# Nano_1.net
KiCad netlist of a schematic drawn in Altium Designer
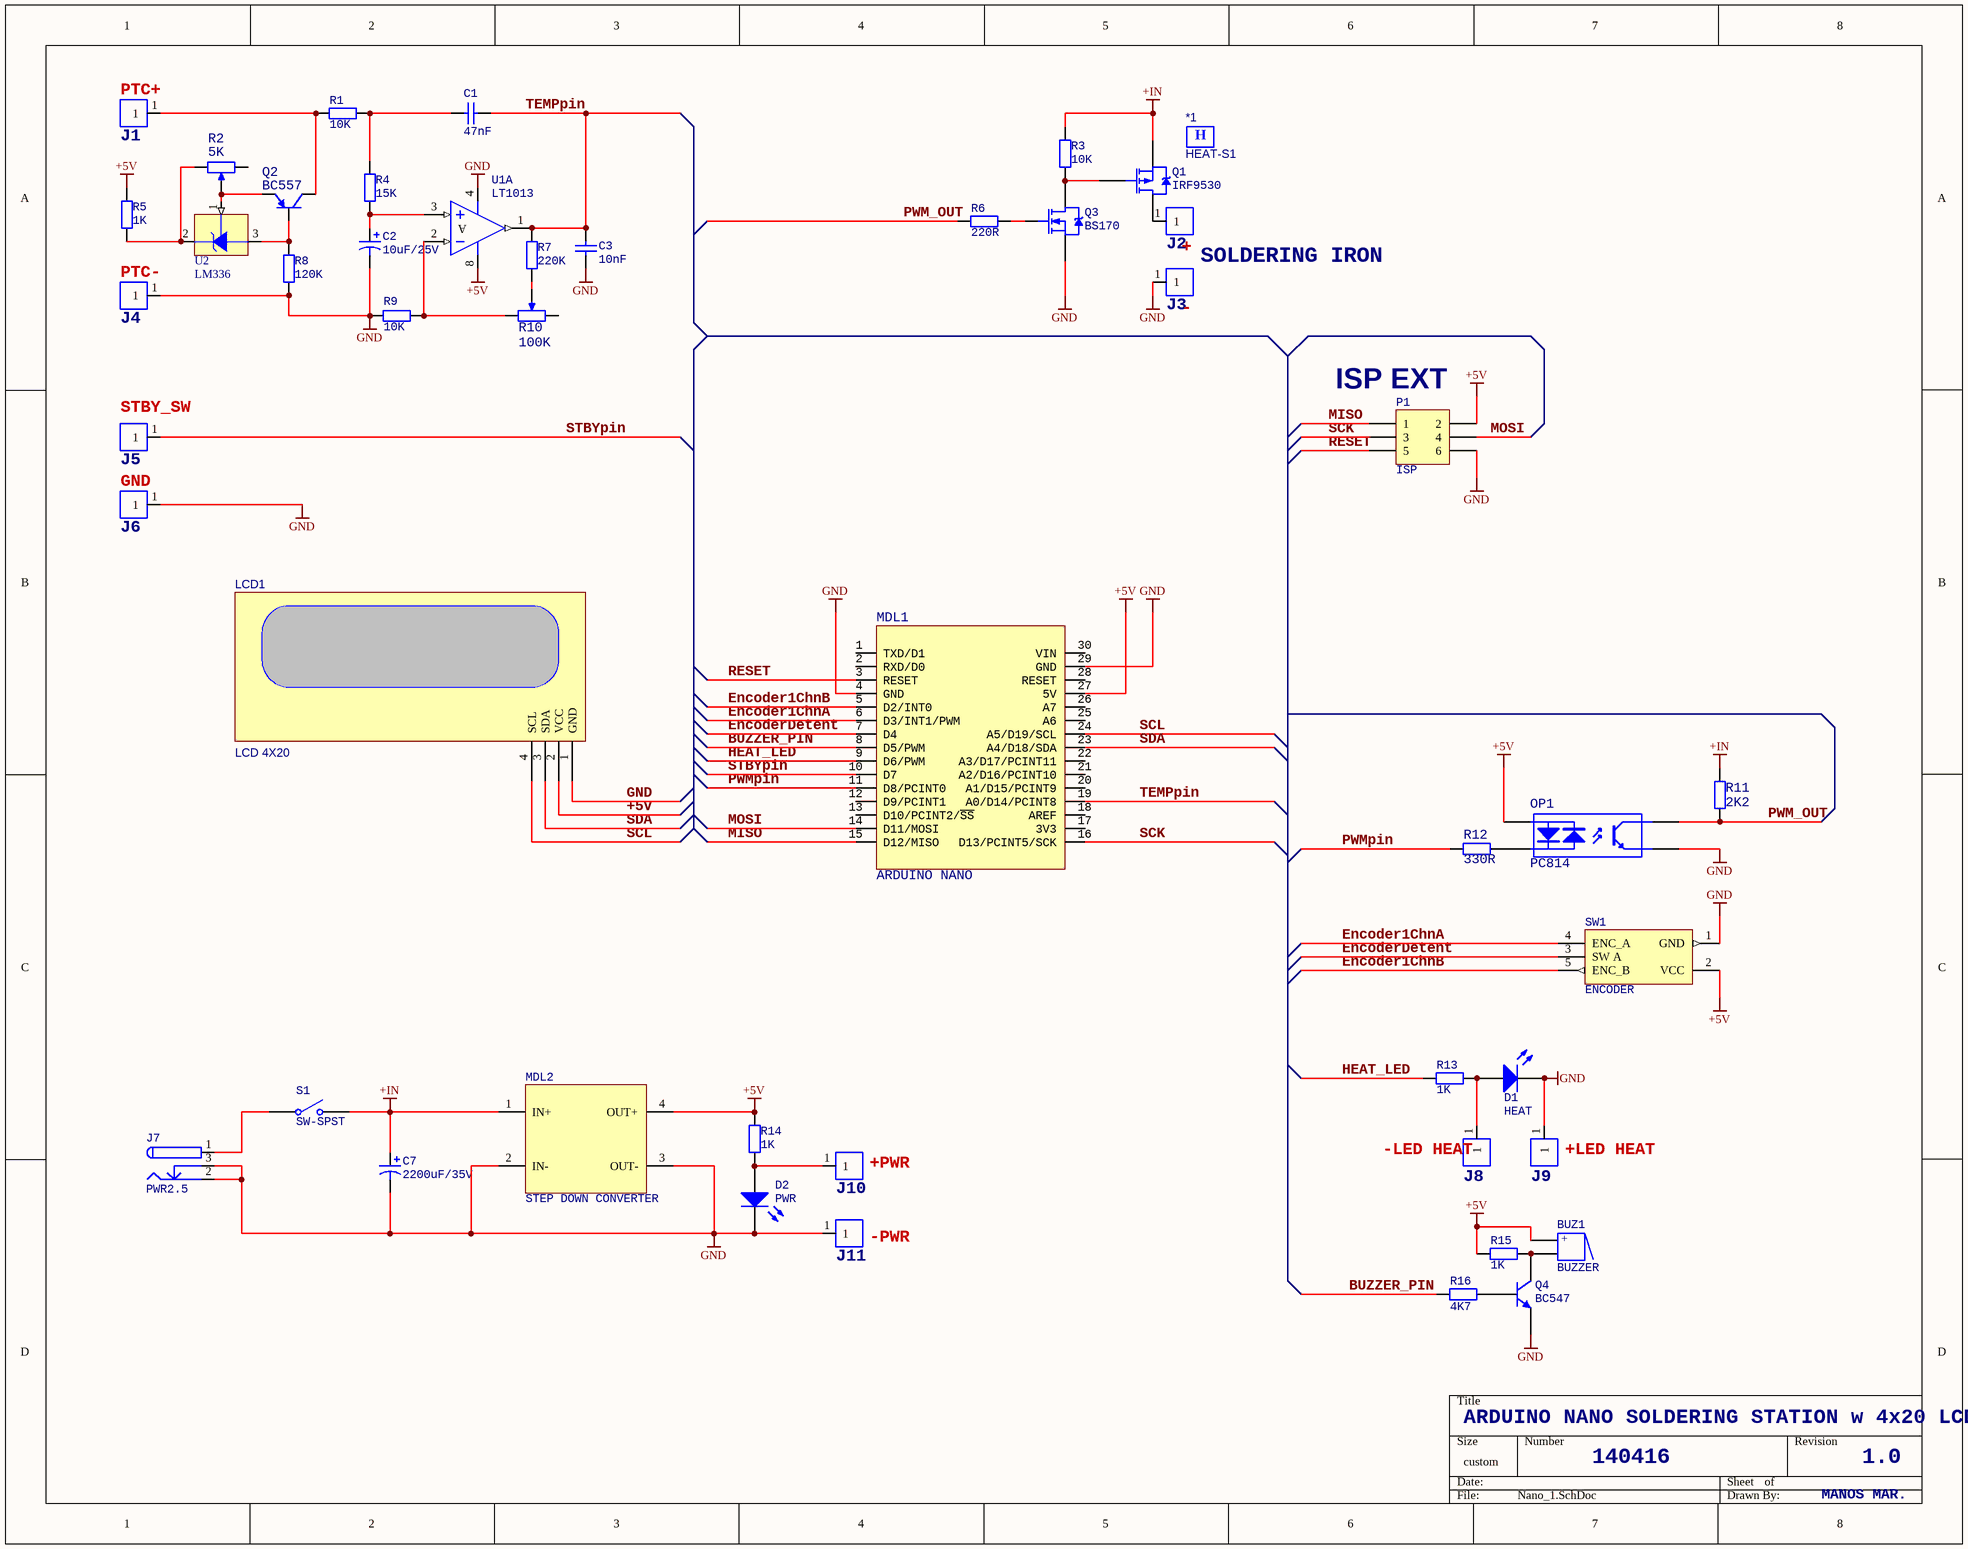
[diagram p0: Nano_1.SchDoc]

(export (version "E")
  (design (tool "Eeschema 10.0.6"))
  (components
    (comp (ref "*1")
      (value "HEAT-S1")
      (footprint "SK 104 HEATSHINK")
      (libsource (lib "SG_INTLIB") (part "HEAT-S1"))
    )
    (comp (ref "BUZ1") (value "BUZZER") (footprint "BUZZER") (libsource (lib "SMD STATION") (part "BUZZER")))
    (comp (ref "C1")
      (value "47nF")
      (footprint "RAD0.2")
      (description "Capacitor, Ceramic, 4.7uF 10% 16V 0805 (2012) X7R")
      (fields (field (name "TOLERANCE") "10 %"))
      (libsource (lib "AltiumDesignLibrary") (part "CAP-NP"))
    )
    (comp (ref "C2")
      (value "10uF/25V")
      (footprint "RB-08")
      (description "Polarized Capacitor (Radial)")
      (fields (field (name "PUBLISHER") "Altium Limited"))
      (libsource (lib "Miscellaneous Devices") (part "Cap Pol1"))
    )
    (comp (ref "C3")
      (value "10nF")
      (footprint "RAD0.2")
      (description "Capacitor, Ceramic, 4.7uF 10% 16V 0805 (2012) X7R")
      (fields (field (name "TOLERANCE") "10 %"))
      (libsource (lib "AltiumDesignLibrary") (part "CAP-NP"))
    )
    (comp (ref "C7")
      (value "2200uF/35V")
      (footprint "RB5-10.5")
      (description "Polarized Capacitor (Radial)")
      (fields (field (name "PUBLISHER") "Altium Limited"))
      (libsource (lib "Miscellaneous Devices") (part "Cap Pol1"))
    )
    (comp (ref "D1")
      (value "HEAT")
      (footprint "LED0.3")
      (description "Typical INFRARED GaAs LED")
      (fields (field (name "PUBLISHER") "Altium Limited"))
      (libsource (lib "Miscellaneous Devices") (part "LED0"))
    )
    (comp (ref "D2")
      (value "PWR")
      (footprint "LED0.3")
      (description "Typical INFRARED GaAs LED")
      (fields (field (name "PUBLISHER") "Altium Limited"))
      (libsource (lib "Miscellaneous Devices") (part "LED0"))
    )
    (comp (ref "J1")
      (value "PTC+")
      (footprint "CON2")
      (fields (field (name "MANUFACTURER") "Sta.Ge HELLAS"))
      (libsource (lib "Z_General_SCH_Library") (part "CON1_S"))
    )
    (comp (ref "J2")
      (value "+")
      (footprint "CON2")
      (fields (field (name "MANUFACTURER") "Sta.Ge HELLAS"))
      (libsource (lib "") (part "CON1_S_1"))
    )
    (comp (ref "J3")
      (value "-")
      (footprint "CON2")
      (fields (field (name "MANUFACTURER") "Sta.Ge HELLAS"))
      (libsource (lib "") (part "CON1_S_1"))
    )
    (comp (ref "J4")
      (value "PTC-")
      (footprint "CON2")
      (fields (field (name "MANUFACTURER") "Sta.Ge HELLAS"))
      (libsource (lib "Z_General_SCH_Library") (part "CON1_S"))
    )
    (comp (ref "J5")
      (value "STBY_SW")
      (footprint "CON2")
      (fields (field (name "MANUFACTURER") "Sta.Ge HELLAS"))
      (libsource (lib "Z_General_SCH_Library") (part "CON1_S"))
    )
    (comp (ref "J6")
      (value "GND")
      (footprint "CON2")
      (fields (field (name "MANUFACTURER") "Sta.Ge HELLAS"))
      (libsource (lib "Z_General_SCH_Library") (part "CON1_S"))
    )
    (comp (ref "J7")
      (value "PWR2.5")
      (footprint "POWER JACK")
      (description "Low Voltage Power Supply Connector")
      (fields (field (name "PUBLISHER") "Altium Limited"))
      (libsource (lib "Miscellaneous Connectors") (part "PWR2.5"))
    )
    (comp (ref "J8")
      (value "-LED HEAT")
      (footprint "CON2")
      (fields (field (name "MANUFACTURER") "Sta.Ge HELLAS"))
      (libsource (lib "") (part "CON1_S_2"))
    )
    (comp (ref "J9")
      (value "+LED HEAT")
      (footprint "CON2")
      (fields (field (name "MANUFACTURER") "Sta.Ge HELLAS"))
      (libsource (lib "") (part "CON1_S_2"))
    )
    (comp (ref "J10")
      (value "+PWR")
      (footprint "CON2")
      (fields (field (name "MANUFACTURER") "Sta.Ge HELLAS"))
      (libsource (lib "") (part "CON1_S_1"))
    )
    (comp (ref "J11")
      (value "-PWR")
      (footprint "CON2")
      (fields (field (name "MANUFACTURER") "Sta.Ge HELLAS"))
      (libsource (lib "") (part "CON1_S_1"))
    )
    (comp (ref "LCD1")
      (value "LCD 4X20")
      (footprint "HDR1X4")
      (fields (field (name "Comment") "LCD 4x20 SERIAL"))
      (libsource (lib "DDS_") (part "LCD4X20"))
    )
    (comp (ref "MDL1")
      (value "ARDUINO NANO")
      (footprint "ARDUINO NANO")
      (libsource (lib "SMD STATION") (part "ARDUINO NANO"))
    )
    (comp (ref "MDL2")
      (value "STEP DOWN CONVERTER")
      (footprint "STEP DOWN CONVERTER MINI")
      (libsource (lib "SMD STATION") (part "STEP DOWN CONVERTER"))
    )
    (comp (ref "OP1")
      (value "PC814")
      (footprint "DIP-4")
      (description "AC OPTOCUPLER")
      (libsource (lib "STAGE_MP3") (part "OPTO-AC1"))
    )
    (comp (ref "P1")
      (value "ISP")
      (footprint "HDR2X3")
      (description "Header, 3-Pin, Dual row")
      (fields (field (name "PUBLISHER") "Altium Limited"))
      (libsource (lib "Miscellaneous Connectors") (part "Header 3X2"))
    )
    (comp (ref "Q1")
      (value "IRF9530")
      (footprint "TO-220V")
      (description "P-Channel Power MOSFET")
      (fields (field (name "PUBLISHER") "Altium Limited"))
      (libsource (lib "Miscellaneous Devices") (part "PMOS-2"))
    )
    (comp (ref "Q2")
      (value "BC557")
      (footprint "T0-92")
      (description "PNP Bipolar Transistor")
      (fields (field (name "PUBLISHER") "Altium Limited"))
      (libsource (lib "Miscellaneous Devices") (part "PNP"))
    )
    (comp (ref "Q3")
      (value "BS170")
      (footprint "T0-92")
      (description "N-Channel Power MOSFET")
      (fields (field (name "PUBLISHER") "Altium Limited"))
      (libsource (lib "Miscellaneous Devices") (part "NMOS-2"))
    )
    (comp (ref "Q4")
      (value "BC547")
      (footprint "T0-92")
      (description "NPN Bipolar Transistor")
      (fields (field (name "PUBLISHER") "Altium Limited"))
      (libsource (lib "Miscellaneous Devices") (part "NPN"))
    )
    (comp (ref "R1")
      (value "10K")
      (footprint "AXIAL0.4")
      (fields
        (field (name "MANUFACTURER") "Generic Components")
        (field (name "POWER") "0,2W")
        (field (name "SGPARTNUMBER") "R001051")
        (field (name "PUBLISHER") "Altium Limited")
      )
      (libsource (lib "") (part "RES_1"))
    )
    (comp (ref "R2")
      (value "5K")
      (footprint "VR6")
      (fields
        (field (name "MANUFACTURER") "Sta.Ge HELLAS")
        (field (name "SGPARTNUMBER") "R001049")
        (field (name "PART NUMBER") "R002107")
        (field (name "PUBLISHER") "Altium Limited")
      )
      (libsource (lib "") (part "RPot2_1"))
    )
    (comp (ref "R3")
      (value "10K")
      (footprint "AXIAL0.4")
      (description "Resistor")
      (fields (field (name "PUBLISHER") "Altium Limited"))
      (libsource (lib "") (part "Res2_1"))
    )
    (comp (ref "R4")
      (value "15K")
      (footprint "AXIAL0.4")
      (fields
        (field (name "MANUFACTURER") "Generic Components")
        (field (name "POWER") "0,2W")
        (field (name "SGPARTNUMBER") "R001051")
        (field (name "PUBLISHER") "Altium Limited")
      )
      (libsource (lib "") (part "RES_3"))
    )
    (comp (ref "R5")
      (value "1K")
      (footprint "AXIAL0.4")
      (fields
        (field (name "MANUFACTURER") "Generic Components")
        (field (name "POWER") "0,2W")
        (field (name "SGPARTNUMBER") "R001051")
        (field (name "PUBLISHER") "Altium Limited")
      )
      (libsource (lib "SG_PCB") (part "RES"))
    )
    (comp (ref "R6")
      (value "220R")
      (footprint "AXIAL0.4")
      (description "Resistor")
      (fields (field (name "PUBLISHER") "Altium Limited"))
      (libsource (lib "Miscellaneous Devices") (part "Res2"))
    )
    (comp (ref "R7")
      (value "220K")
      (footprint "AXIAL0.4")
      (fields
        (field (name "MANUFACTURER") "Generic Components")
        (field (name "POWER") "0,2W")
        (field (name "SGPARTNUMBER") "R001051")
        (field (name "PUBLISHER") "Altium Limited")
      )
      (libsource (lib "") (part "RES_3"))
    )
    (comp (ref "R8")
      (value "120K")
      (footprint "AXIAL0.4")
      (fields
        (field (name "MANUFACTURER") "Generic Components")
        (field (name "POWER") "0,2W")
        (field (name "SGPARTNUMBER") "R001051")
        (field (name "PUBLISHER") "Altium Limited")
      )
      (libsource (lib "SG_PCB") (part "RES"))
    )
    (comp (ref "R9")
      (value "10K")
      (footprint "AXIAL0.4")
      (fields
        (field (name "MANUFACTURER") "Generic Components")
        (field (name "POWER") "0,2W")
        (field (name "SGPARTNUMBER") "R001051")
        (field (name "PUBLISHER") "Altium Limited")
      )
      (libsource (lib "") (part "RES_2"))
    )
    (comp (ref "R10")
      (value "100K")
      (footprint "VR6")
      (fields
        (field (name "MANUFACTURER") "Sta.Ge HELLAS")
        (field (name "SGPARTNUMBER") "R001049")
        (field (name "PART NUMBER") "R002107")
        (field (name "PUBLISHER") "Altium Limited")
      )
      (libsource (lib "SG_INTLIB") (part "RPot2"))
    )
    (comp (ref "R11")
      (value "2K2")
      (footprint "AXIAL0.4")
      (fields
        (field (name "MANUFACTURER") "Generic Components")
        (field (name "POWER") "0,2W")
        (field (name "SGPARTNUMBER") "R001051")
        (field (name "PUBLISHER") "Altium Limited")
      )
      (libsource (lib "") (part "RES_3"))
    )
    (comp (ref "R12")
      (value "330R")
      (footprint "AXIAL0.4")
      (fields
        (field (name "MANUFACTURER") "Generic Components")
        (field (name "POWER") "0,2W")
        (field (name "SGPARTNUMBER") "R001051")
        (field (name "PUBLISHER") "Altium Limited")
      )
      (libsource (lib "") (part "RES_2"))
    )
    (comp (ref "R13")
      (value "1K")
      (footprint "AXIAL0.4")
      (description "Resistor")
      (fields (field (name "PUBLISHER") "Altium Limited"))
      (libsource (lib "Miscellaneous Devices") (part "Res2"))
    )
    (comp (ref "R14")
      (value "1K")
      (footprint "AXIAL0.4")
      (description "Resistor")
      (fields (field (name "PUBLISHER") "Altium Limited"))
      (libsource (lib "") (part "Res2_1"))
    )
    (comp (ref "R15")
      (value "1K")
      (footprint "AXIAL0.4")
      (fields
        (field (name "MANUFACTURER") "Generic Components")
        (field (name "POWER") "0,2W")
        (field (name "SGPARTNUMBER") "R001051")
        (field (name "PUBLISHER") "Altium Limited")
      )
      (libsource (lib "") (part "RES_2"))
    )
    (comp (ref "R16")
      (value "4K7")
      (footprint "AXIAL0.4")
      (fields
        (field (name "MANUFACTURER") "Generic Components")
        (field (name "POWER") "0,2W")
        (field (name "SGPARTNUMBER") "R001051")
        (field (name "PUBLISHER") "Altium Limited")
      )
      (libsource (lib "") (part "RES_1"))
    )
    (comp (ref "S1")
      (value "SW-SPST")
      (footprint "SPST-2")
      (description "Single-Pole, Single-Throw Switch")
      (fields (field (name "PUBLISHER") "Altium Limited"))
      (libsource (lib "Miscellaneous Devices") (part "SW-SPST"))
    )
    (comp (ref "SW1")
      (value "ENCODER")
      (footprint "HDR1X5")
      (libsource (lib "SMD STATION") (part "ROTARY ENC"))
    )
    (comp (ref "U1")
      (value "LT1013")
      (footprint "DIP-8")
      (description "Dual Precision Operational Amplifier")
      (fields (field (name "PUBLISHER") "Altium Limited"))
      (libsource (lib "LT Operational Amplifier") (part "LT1013ACJ8"))
    )
    (comp (ref "U2")
      (value "LM336")
      (footprint "Z03A")
      (description "Adjustable Micropower Voltage Reference")
      (fields (field (name "PUBLISHER") "Altium Limited"))
      (libsource (lib "NSC Power Mgt Voltage Reference") (part "LM385Z"))
    )
  )
  (nets
    (net (code "1") (name "+5V") (class "Default")
      (node (ref "BUZ1") (pin "1") (pinfunction "1_1") (pintype "passive"))
      (node (ref "LCD1") (pin "2") (pinfunction "VCC_2") (pintype "passive"))
      (node (ref "MDL1") (pin "27") (pinfunction "5V_27") (pintype "passive"))
      (node (ref "MDL2") (pin "4") (pinfunction "OUT+_4") (pintype "passive"))
      (node (ref "OP1") (pin "1") (pinfunction "A_1") (pintype "passive"))
      (node (ref "P1") (pin "2") (pinfunction "2_2") (pintype "passive"))
      (node (ref "R14") (pin "2") (pinfunction "2_2") (pintype "passive"))
      (node (ref "R15") (pin "2") (pinfunction "2_2") (pintype "passive"))
      (node (ref "R5") (pin "2") (pinfunction "2_2") (pintype "passive"))
      (node (ref "SW1") (pin "2") (pinfunction "VCC_2") (pintype "passive"))
      (node (ref "U1") (pin "8") (pinfunction "V+_8") (pintype "power_in"))
    )
    (net (code "2") (name "+IN") (class "Default")
      (node (ref "C7") (pin "1") (pinfunction "1_1") (pintype "passive"))
      (node (ref "MDL2") (pin "1") (pinfunction "IN+_1") (pintype "passive"))
      (node (ref "Q1") (pin "3") (pinfunction "S_3") (pintype "passive"))
      (node (ref "R11") (pin "1") (pinfunction "1_1") (pintype "passive"))
      (node (ref "R3") (pin "2") (pinfunction "2_2") (pintype "passive"))
      (node (ref "S1") (pin "2") (pinfunction "NO_2") (pintype "passive"))
    )
    (net (code "3") (name "/BUZZER_PIN") (class "Default")
      (node (ref "MDL1") (pin "8") (pinfunction "D5/PWM_8") (pintype "passive"))
      (node (ref "R16") (pin "1") (pinfunction "1_1") (pintype "passive"))
    )
    (net (code "4") (name "/Encoder1ChnA") (class "Default")
      (node (ref "MDL1") (pin "6") (pinfunction "D3/INT1/PWM_6") (pintype "passive"))
      (node (ref "SW1") (pin "4") (pinfunction "ENC_A_4") (pintype "passive"))
    )
    (net (code "5") (name "/Encoder1ChnB") (class "Default")
      (node (ref "MDL1") (pin "5") (pinfunction "D2/INT0_5") (pintype "passive"))
      (node (ref "SW1") (pin "5") (pinfunction "ENC_B_5") (pintype "output"))
    )
    (net (code "6") (name "/EncoderDetent") (class "Default")
      (node (ref "MDL1") (pin "7") (pinfunction "D4_7") (pintype "passive"))
      (node (ref "SW1") (pin "3") (pinfunction "SW_A_3") (pintype "passive"))
    )
    (net (code "7") (name "/HEAT_LED") (class "Default")
      (node (ref "MDL1") (pin "9") (pinfunction "D6/PWM_9") (pintype "passive"))
      (node (ref "R13") (pin "1") (pinfunction "1_1") (pintype "passive"))
    )
    (net (code "8") (name "/MISO") (class "Default")
      (node (ref "MDL1") (pin "15") (pinfunction "D12/MISO_15") (pintype "passive"))
      (node (ref "P1") (pin "1") (pinfunction "1_1") (pintype "passive"))
    )
    (net (code "9") (name "/MOSI") (class "Default")
      (node (ref "MDL1") (pin "14") (pinfunction "D11/MOSI_14") (pintype "passive"))
      (node (ref "P1") (pin "4") (pinfunction "4_4") (pintype "passive"))
    )
    (net (code "10") (name "/PWM_OUT") (class "Default")
      (node (ref "OP1") (pin "4") (pinfunction "C_4") (pintype "passive"))
      (node (ref "R11") (pin "2") (pinfunction "2_2") (pintype "passive"))
      (node (ref "R6") (pin "1") (pinfunction "1_1") (pintype "passive"))
    )
    (net (code "11") (name "/PWMpin") (class "Default")
      (node (ref "MDL1") (pin "11") (pinfunction "D8/PCINT0_11") (pintype "passive"))
      (node (ref "R12") (pin "2") (pinfunction "2_2") (pintype "passive"))
    )
    (net (code "12") (name "/RESET") (class "Default")
      (node (ref "MDL1") (pin "3") (pinfunction "RESET_3") (pintype "passive"))
      (node (ref "P1") (pin "5") (pinfunction "5_5") (pintype "passive"))
    )
    (net (code "13") (name "/SCK") (class "Default")
      (node (ref "MDL1") (pin "16") (pinfunction "D13/PCINT5/SCK_16") (pintype "passive"))
      (node (ref "P1") (pin "3") (pinfunction "3_3") (pintype "passive"))
    )
    (net (code "14") (name "/SCL") (class "Default")
      (node (ref "LCD1") (pin "4") (pinfunction "SCL_4") (pintype "passive"))
      (node (ref "MDL1") (pin "24") (pinfunction "A5/D19/SCL_24") (pintype "passive"))
    )
    (net (code "15") (name "/SDA") (class "Default")
      (node (ref "LCD1") (pin "3") (pinfunction "SDA_3") (pintype "passive"))
      (node (ref "MDL1") (pin "23") (pinfunction "A4/D18/SDA_23") (pintype "passive"))
    )
    (net (code "16") (name "/STBYpin") (class "Default")
      (node (ref "J5") (pin "1") (pinfunction "1_1") (pintype "passive"))
      (node (ref "MDL1") (pin "10") (pinfunction "D7_10") (pintype "passive"))
    )
    (net (code "17") (name "/TEMPpin") (class "Default")
      (node (ref "C1") (pin "1") (pinfunction "1_1") (pintype "passive"))
      (node (ref "C3") (pin "2") (pinfunction "2_2") (pintype "passive"))
      (node (ref "MDL1") (pin "19") (pinfunction "A0/D14/PCINT8_19") (pintype "passive"))
      (node (ref "R7") (pin "1") (pinfunction "1_1") (pintype "passive"))
      (node (ref "U1") (pin "1") (pinfunction "OUT_1") (pintype "output"))
    )
    (net (code "18") (name "GND") (class "Default")
      (node (ref "C2") (pin "2") (pinfunction "2_2") (pintype "passive"))
      (node (ref "C3") (pin "1") (pinfunction "1_1") (pintype "passive"))
      (node (ref "C7") (pin "2") (pinfunction "2_2") (pintype "passive"))
      (node (ref "D1") (pin "2") (pinfunction "K_2") (pintype "passive"))
      (node (ref "D2") (pin "2") (pinfunction "K_2") (pintype "passive"))
      (node (ref "J11") (pin "1") (pinfunction "1_1") (pintype "passive"))
      (node (ref "J3") (pin "1") (pinfunction "1_1") (pintype "passive"))
      (node (ref "J4") (pin "1") (pinfunction "1_1") (pintype "passive"))
      (node (ref "J6") (pin "1") (pinfunction "1_1") (pintype "passive"))
      (node (ref "J7") (pin "2") (pinfunction "2_2") (pintype "power_in"))
      (node (ref "J7") (pin "3") (pinfunction "3_3") (pintype "power_in"))
      (node (ref "J9") (pin "1") (pinfunction "1_1") (pintype "passive"))
      (node (ref "LCD1") (pin "1") (pinfunction "GND_1") (pintype "passive"))
      (node (ref "MDL1") (pin "29") (pinfunction "GND_29") (pintype "passive"))
      (node (ref "MDL1") (pin "4") (pinfunction "GND_4") (pintype "passive"))
      (node (ref "MDL2") (pin "2") (pinfunction "IN-_2") (pintype "passive"))
      (node (ref "MDL2") (pin "3") (pinfunction "OUT-_3") (pintype "passive"))
      (node (ref "OP1") (pin "3") (pinfunction "E_3") (pintype "passive"))
      (node (ref "P1") (pin "6") (pinfunction "6_6") (pintype "passive"))
      (node (ref "Q3") (pin "3") (pinfunction "S_3") (pintype "passive"))
      (node (ref "Q4") (pin "2") (pinfunction "E_2") (pintype "passive"))
      (node (ref "R8") (pin "1") (pinfunction "1_1") (pintype "passive"))
      (node (ref "R9") (pin "2") (pinfunction "2_2") (pintype "passive"))
      (node (ref "SW1") (pin "1") (pinfunction "GND_1") (pintype "output"))
      (node (ref "U1") (pin "4") (pinfunction "V-_4") (pintype "power_in"))
    )
    (net (code "19") (name "Net-(C1-Pad2)") (class "Default")
      (node (ref "C1") (pin "2") (pinfunction "2_2") (pintype "passive"))
      (node (ref "R1") (pin "2") (pinfunction "2_2") (pintype "passive"))
      (node (ref "R4") (pin "1") (pinfunction "1_1") (pintype "passive"))
    )
    (net (code "20") (name "Net-(D1-A)") (class "Default")
      (node (ref "D1") (pin "1") (pinfunction "A_1") (pintype "passive"))
      (node (ref "J8") (pin "1") (pinfunction "1_1") (pintype "passive"))
      (node (ref "R13") (pin "2") (pinfunction "2_2") (pintype "passive"))
    )
    (net (code "21") (name "Net-(D2-A)") (class "Default")
      (node (ref "D2") (pin "1") (pinfunction "A_1") (pintype "passive"))
      (node (ref "J10") (pin "1") (pinfunction "1_1") (pintype "passive"))
      (node (ref "R14") (pin "1") (pinfunction "1_1") (pintype "passive"))
    )
    (net (code "22") (name "Net-(OP1-K)") (class "Default")
      (node (ref "OP1") (pin "2") (pinfunction "K_2") (pintype "passive"))
      (node (ref "R12") (pin "1") (pinfunction "1_1") (pintype "passive"))
    )
    (net (code "23") (name "Net-(Q1-D)") (class "Default")
      (node (ref "J2") (pin "1") (pinfunction "1_1") (pintype "passive"))
      (node (ref "Q1") (pin "2") (pinfunction "D_2") (pintype "passive"))
    )
    (net (code "24") (name "Net-(Q1-G)") (class "Default")
      (node (ref "Q1") (pin "1") (pinfunction "G_1") (pintype "passive"))
      (node (ref "Q3") (pin "2") (pinfunction "D_2") (pintype "passive"))
      (node (ref "R3") (pin "1") (pinfunction "1_1") (pintype "passive"))
    )
    (net (code "25") (name "Net-(Q2-B)") (class "Default")
      (node (ref "Q2") (pin "1") (pinfunction "B_1") (pintype "passive"))
      (node (ref "R8") (pin "2") (pinfunction "2_2") (pintype "passive"))
      (node (ref "U2") (pin "3") (pinfunction "-V_3") (pintype "passive"))
    )
    (net (code "26") (name "Net-(Q2-C)") (class "Default")
      (node (ref "J1") (pin "1") (pinfunction "1_1") (pintype "passive"))
      (node (ref "Q2") (pin "3") (pinfunction "C_3") (pintype "passive"))
      (node (ref "R1") (pin "1") (pinfunction "1_1") (pintype "passive"))
    )
    (net (code "27") (name "Net-(Q2-E)") (class "Default")
      (node (ref "Q2") (pin "2") (pinfunction "E_2") (pintype "passive"))
      (node (ref "R2") (pin "2") (pinfunction "TAP_2") (pintype "passive"))
      (node (ref "U2") (pin "1") (pinfunction "ADJ_1") (pintype "input"))
    )
    (net (code "28") (name "Net-(Q3-G)") (class "Default")
      (node (ref "Q3") (pin "1") (pinfunction "G_1") (pintype "passive"))
      (node (ref "R6") (pin "2") (pinfunction "2_2") (pintype "passive"))
    )
    (net (code "29") (name "Net-(Q4-B)") (class "Default")
      (node (ref "Q4") (pin "1") (pinfunction "B_1") (pintype "passive"))
      (node (ref "R16") (pin "2") (pinfunction "2_2") (pintype "passive"))
    )
    (net (code "30") (name "Net-(Q4-C)") (class "Default")
      (node (ref "BUZ1") (pin "2") (pinfunction "2_2") (pintype "passive"))
      (node (ref "Q4") (pin "3") (pinfunction "C_3") (pintype "passive"))
      (node (ref "R15") (pin "1") (pinfunction "1_1") (pintype "passive"))
    )
    (net (code "31") (name "Net-(R2-TOP)") (class "Default")
      (node (ref "R2") (pin "1") (pinfunction "TOP_1") (pintype "passive"))
      (node (ref "R5") (pin "1") (pinfunction "1_1") (pintype "passive"))
      (node (ref "U2") (pin "2") (pinfunction "+V_2") (pintype "passive"))
    )
    (net (code "32") (name "Net-(R10-BOT)") (class "Default")
      (node (ref "R10") (pin "1") (pinfunction "BOT_1") (pintype "passive"))
      (node (ref "R9") (pin "1") (pinfunction "1_1") (pintype "passive"))
      (node (ref "U1") (pin "2") (pinfunction "IN-_2") (pintype "input"))
    )
    (net (code "33") (name "Net-(R10-TAP)") (class "Default")
      (node (ref "R10") (pin "2") (pinfunction "TAP_2") (pintype "passive"))
      (node (ref "R7") (pin "2") (pinfunction "2_2") (pintype "passive"))
    )
    (net (code "34") (name "Net-(S1-COMMON)") (class "Default")
      (node (ref "J7") (pin "1") (pinfunction "1_1") (pintype "power_in"))
      (node (ref "S1") (pin "1") (pinfunction "COMMON_1") (pintype "passive"))
    )
    (net (code "35") (name "Net-(U1A-IN+)") (class "Default")
      (node (ref "C2") (pin "1") (pinfunction "1_1") (pintype "passive"))
      (node (ref "R4") (pin "2") (pinfunction "2_2") (pintype "passive"))
      (node (ref "U1") (pin "3") (pinfunction "IN+_3") (pintype "input"))
    )
    (net (code "36") (name "unconnected-(MDL1-3V3-Pad17)") (class "Default")
      (node (ref "MDL1") (pin "17") (pinfunction "3V3_17") (pintype "passive"))
    )
    (net (code "37") (name "unconnected-(MDL1-A1{slash}D15{slash}PCINT9-Pad20)") (class "Default")
      (node (ref "MDL1") (pin "20") (pinfunction "A1/D15/PCINT9_20") (pintype "passive"))
    )
    (net (code "38") (name "unconnected-(MDL1-A2{slash}D16{slash}PCINT10-Pad21)") (class "Default")
      (node (ref "MDL1") (pin "21") (pinfunction "A2/D16/PCINT10_21") (pintype "passive"))
    )
    (net (code "39") (name "unconnected-(MDL1-A3{slash}D17{slash}PCINT11-Pad22)") (class "Default")
      (node (ref "MDL1") (pin "22") (pinfunction "A3/D17/PCINT11_22") (pintype "passive"))
    )
    (net (code "40") (name "unconnected-(MDL1-A6-Pad25)") (class "Default")
      (node (ref "MDL1") (pin "25") (pinfunction "A6_25") (pintype "passive"))
    )
    (net (code "41") (name "unconnected-(MDL1-A7-Pad26)") (class "Default")
      (node (ref "MDL1") (pin "26") (pinfunction "A7_26") (pintype "passive"))
    )
    (net (code "42") (name "unconnected-(MDL1-AREF-Pad18)") (class "Default")
      (node (ref "MDL1") (pin "18") (pinfunction "AREF_18") (pintype "passive"))
    )
    (net (code "43") (name "unconnected-(MDL1-D9{slash}PCINT1-Pad12)") (class "Default")
      (node (ref "MDL1") (pin "12") (pinfunction "D9/PCINT1_12") (pintype "passive"))
    )
    (net (code "44") (name "unconnected-(MDL1-D10{slash}PCINT2{slash}~{SS}-Pad13)") (class "Default")
      (node (ref "MDL1") (pin "13") (pinfunction "D10/PCINT2/~{SS}_13") (pintype "passive"))
    )
    (net (code "45") (name "unconnected-(MDL1-RESET-Pad28)") (class "Default")
      (node (ref "MDL1") (pin "28") (pinfunction "RESET_28") (pintype "passive"))
    )
    (net (code "46") (name "unconnected-(MDL1-RXD{slash}D0-Pad2)") (class "Default")
      (node (ref "MDL1") (pin "2") (pinfunction "RXD/D0_2") (pintype "passive"))
    )
    (net (code "47") (name "unconnected-(MDL1-TXD{slash}D1-Pad1)") (class "Default")
      (node (ref "MDL1") (pin "1") (pinfunction "TXD/D1_1") (pintype "passive"))
    )
    (net (code "48") (name "unconnected-(MDL1-VIN-Pad30)") (class "Default")
      (node (ref "MDL1") (pin "30") (pinfunction "VIN_30") (pintype "passive"))
    )
    (net (code "49") (name "unconnected-(R2-BOT-Pad3)") (class "Default")
      (node (ref "R2") (pin "3") (pinfunction "BOT_3") (pintype "passive"))
    )
    (net (code "50") (name "unconnected-(R10-TOP-Pad3)") (class "Default")
      (node (ref "R10") (pin "3") (pinfunction "TOP_3") (pintype "passive"))
    )
  )
)
